# H-bro_gear.net
KiCad netlist of a schematic drawn in EAGLE
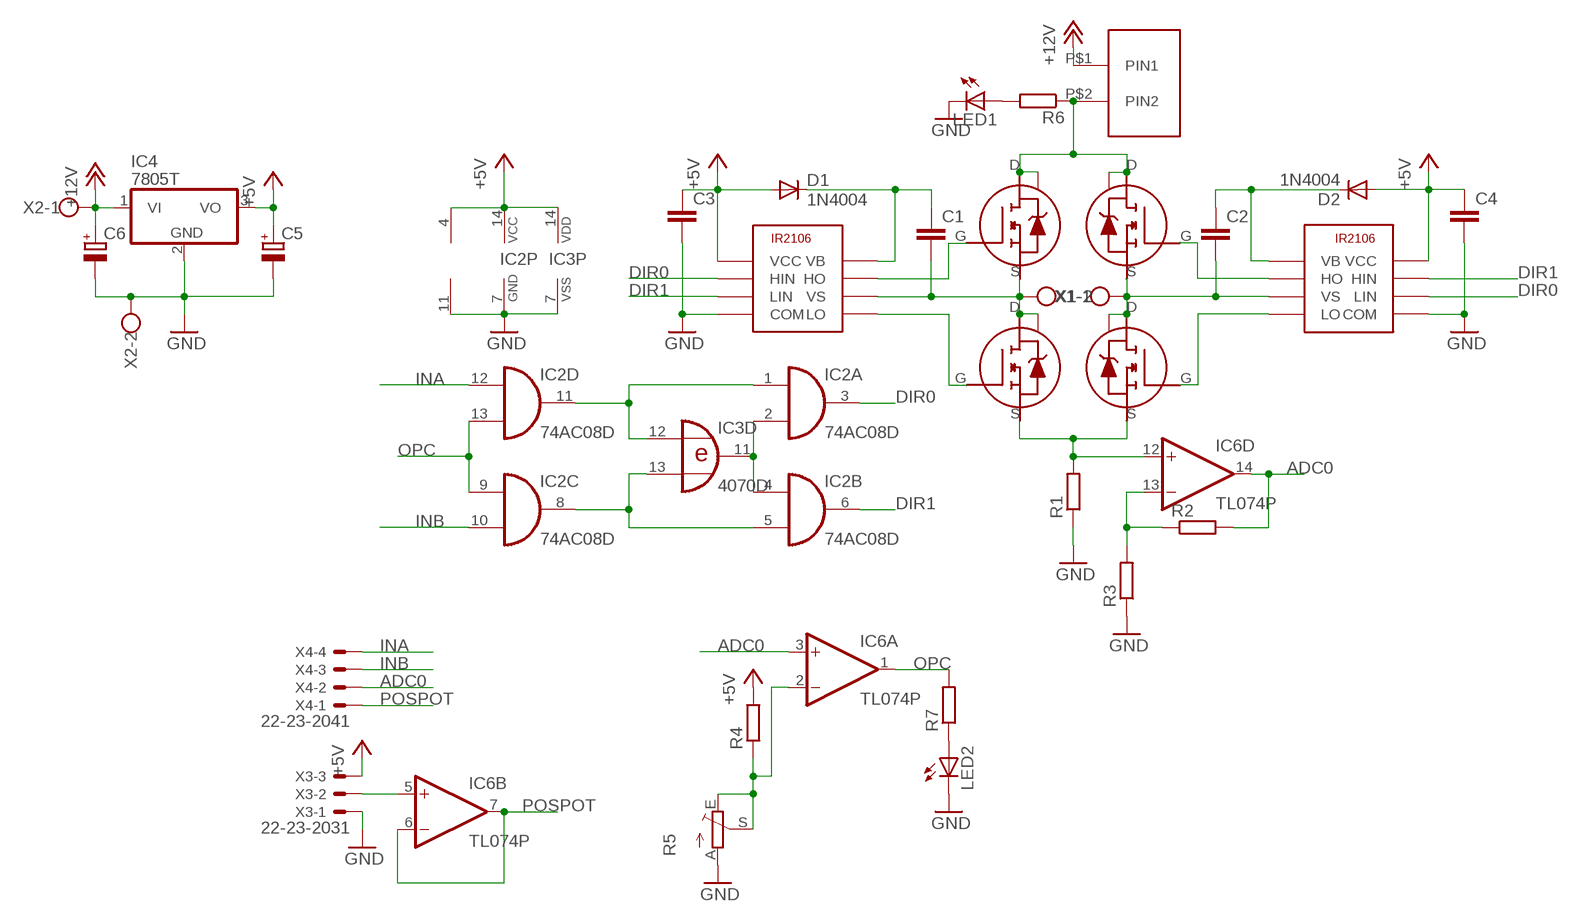
[diagram p0: schematic, sheet 1]

(export (version "E")
  (design (tool "Eeschema 10.0.6"))
  (components
    (comp (ref "C1")
      (value "C-EU050-025X075")
      (footprint "eagle-import:C050-025X075")
      (libsource (lib "eagle-import") (part "C-EU050-025X075"))
    )
    (comp (ref "C2")
      (value "C-EU050-025X075")
      (footprint "eagle-import:C050-025X075")
      (libsource (lib "eagle-import") (part "C-EU050-025X075"))
    )
    (comp (ref "C3")
      (value "C-EU050-025X075")
      (footprint "eagle-import:C050-025X075")
      (libsource (lib "eagle-import") (part "C-EU050-025X075"))
    )
    (comp (ref "C4")
      (value "C-EU050-025X075")
      (footprint "eagle-import:C050-025X075")
      (libsource (lib "eagle-import") (part "C-EU050-025X075"))
    )
    (comp (ref "C5")
      (value "CPOL-EUE15-5AXIAL")
      (footprint "eagle-import:E15-5")
      (libsource (lib "eagle-import") (part "CPOL-EUE15-5AXIAL"))
    )
    (comp (ref "C6")
      (value "CPOL-EUE15-5AXIAL")
      (footprint "eagle-import:E15-5")
      (libsource (lib "eagle-import") (part "CPOL-EUE15-5AXIAL"))
    )
    (comp (ref "D1")
      (value "1N4004")
      (footprint "eagle-import:DO41-10")
      (libsource (lib "eagle-import") (part "1N4004"))
    )
    (comp (ref "D2")
      (value "1N4004")
      (footprint "eagle-import:DO41-10")
      (libsource (lib "eagle-import") (part "1N4004"))
    )
    (comp (ref "IC2")
      (value "74AC08D")
      (footprint "eagle-import:SO14")
      (libsource (lib "eagle-import") (part "7408DAC"))
    )
    (comp (ref "IC3")
      (value "4070D")
      (footprint "eagle-import:SO14")
      (libsource (lib "eagle-import") (part "4070D"))
    )
    (comp (ref "IC4")
      (value "7805T")
      (footprint "eagle-import:TO220H")
      (libsource (lib "eagle-import") (part "78T05"))
    )
    (comp (ref "IC6")
      (value "TL074P")
      (footprint "eagle-import:DIL14")
      (libsource (lib "eagle-import") (part "TL074P"))
    )
    (comp (ref "LED1")
      (value "LED5MM")
      (footprint "eagle-import:LED5MM")
      (libsource (lib "eagle-import") (part "LED5MM"))
    )
    (comp (ref "LED2")
      (value "LED5MM")
      (footprint "eagle-import:LED5MM")
      (libsource (lib "eagle-import") (part "LED5MM"))
    )
    (comp (ref "R1")
      (value "R-EU_0309/12")
      (footprint "eagle-import:0309_12")
      (libsource (lib "eagle-import") (part "resistor_R-EU_0309/12"))
    )
    (comp (ref "R2")
      (value "R-EU_0204/7")
      (footprint "eagle-import:0204_7")
      (libsource (lib "eagle-import") (part "R-EU_0204/7"))
    )
    (comp (ref "R3")
      (value "R-EU_0204/7")
      (footprint "eagle-import:0204_7")
      (libsource (lib "eagle-import") (part "R-EU_0204/7"))
    )
    (comp (ref "R4")
      (value "R-EU_0204/7")
      (footprint "eagle-import:0204_7")
      (libsource (lib "eagle-import") (part "R-EU_0204/7"))
    )
    (comp (ref "R5")
      (value "TRIM_EU-RJ9W")
      (footprint "eagle-import:RJ9W")
      (libsource (lib "eagle-import") (part "TRIM_EU-RJ9W"))
    )
    (comp (ref "R6")
      (value "R-EU_0204/7")
      (footprint "eagle-import:0204_7")
      (libsource (lib "eagle-import") (part "R-EU_0204/7"))
    )
    (comp (ref "R7")
      (value "R-EU_0204/7")
      (footprint "eagle-import:0204_7")
      (libsource (lib "eagle-import") (part "R-EU_0204/7"))
    )
    (comp (ref "U$1")
      (value "IR2106")
      (footprint "eagle-import:IR2106")
      (libsource (lib "eagle-import") (part "IR2106"))
    )
    (comp (ref "U$2")
      (value "IR2106")
      (footprint "eagle-import:IR2106")
      (libsource (lib "eagle-import") (part "IR2106"))
    )
    (comp (ref "U$3")
      (value "STU95N5")
      (footprint "eagle-import:STU95N5")
      (libsource (lib "eagle-import") (part "STU95N5"))
    )
    (comp (ref "U$4")
      (value "STU95N5")
      (footprint "eagle-import:STU95N5")
      (libsource (lib "eagle-import") (part "STU95N5"))
    )
    (comp (ref "U$5")
      (value "STU95N5")
      (footprint "eagle-import:STU95N5")
      (libsource (lib "eagle-import") (part "STU95N5"))
    )
    (comp (ref "U$6")
      (value "STU95N5")
      (footprint "eagle-import:STU95N5")
      (libsource (lib "eagle-import") (part "STU95N5"))
    )
    (comp (ref "U$7")
      (value "LITTE_FUSE")
      (footprint "eagle-import:LITTE_FUSE_PAC")
      (libsource (lib "eagle-import") (part "LITTE_FUSE"))
    )
    (comp (ref "X1")
      (value "W237-102")
      (footprint "eagle-import:W237-102")
      (fields (field (name "MPN") "237-102"))
      (libsource (lib "eagle-import") (part "W237-102"))
    )
    (comp (ref "X2")
      (value "W237-102")
      (footprint "eagle-import:W237-102")
      (fields (field (name "MPN") "237-102"))
      (libsource (lib "eagle-import") (part "W237-102"))
    )
    (comp (ref "X3")
      (value "22-23-2031")
      (footprint "eagle-import:22-23-2031")
      (fields (field (name "MF") "MOLEX"))
      (libsource (lib "eagle-import") (part "22-23-2031"))
    )
    (comp (ref "X4")
      (value "22-23-2041")
      (footprint "eagle-import:22-23-2041")
      (fields (field (name "MF") "MOLEX"))
      (libsource (lib "eagle-import") (part "22-23-2041"))
    )
  )
  (nets
    (net (code "1") (name "+5V") (class "Default")
      (node (ref "C3") (pin "1") (pinfunction "1_1") (pintype "passive"))
      (node (ref "C4") (pin "1") (pinfunction "1_1") (pintype "passive"))
      (node (ref "C5") (pin "+") (pinfunction "+_+") (pintype "passive"))
      (node (ref "D1") (pin "A") (pinfunction "A_A") (pintype "passive"))
      (node (ref "D2") (pin "A") (pinfunction "A_A") (pintype "passive"))
      (node (ref "IC2") (pin "14") (pinfunction "VCC_14") (pintype "power_in"))
      (node (ref "IC3") (pin "14") (pinfunction "VDD_14") (pintype "power_in"))
      (node (ref "IC4") (pin "3") (pinfunction "VO_3") (pintype "passive"))
      (node (ref "IC6") (pin "4") (pinfunction "V+_4") (pintype "power_in"))
      (node (ref "R4") (pin "2") (pinfunction "2_2") (pintype "passive"))
      (node (ref "U$1") (pin "VCC") (pinfunction "VCC_VCC") (pintype "bidirectional"))
      (node (ref "U$2") (pin "VCC") (pinfunction "VCC_VCC") (pintype "bidirectional"))
      (node (ref "X3") (pin "3") (pinfunction "S_3") (pintype "passive"))
    )
    (net (code "2") (name "+12V") (class "Default")
      (node (ref "C6") (pin "+") (pinfunction "+_+") (pintype "passive"))
      (node (ref "IC4") (pin "1") (pinfunction "VI_1") (pintype "input"))
      (node (ref "U$7") (pin "P$1") (pinfunction "PIN1_P$1") (pintype "bidirectional"))
      (node (ref "X2") (pin "1") (pinfunction "KL_1") (pintype "passive"))
    )
    (net (code "3") (name "/ADC0") (class "Default")
      (node (ref "IC6") (pin "14") (pinfunction "OUT_14") (pintype "output"))
      (node (ref "IC6") (pin "3") (pinfunction "+IN_3") (pintype "input"))
      (node (ref "R2") (pin "2") (pinfunction "2_2") (pintype "passive"))
      (node (ref "X4") (pin "2") (pinfunction "S_2") (pintype "passive"))
    )
    (net (code "4") (name "/DIR0") (class "Default")
      (node (ref "IC2") (pin "3") (pinfunction "O_3") (pintype "output"))
      (node (ref "U$1") (pin "HIN") (pinfunction "HIN_HIN") (pintype "bidirectional"))
      (node (ref "U$2") (pin "LIN") (pinfunction "LIN_LIN") (pintype "bidirectional"))
    )
    (net (code "5") (name "/DIR1") (class "Default")
      (node (ref "IC2") (pin "6") (pinfunction "O_6") (pintype "output"))
      (node (ref "U$1") (pin "LIN") (pinfunction "LIN_LIN") (pintype "bidirectional"))
      (node (ref "U$2") (pin "HIN") (pinfunction "HIN_HIN") (pintype "bidirectional"))
    )
    (net (code "6") (name "/INA") (class "Default")
      (node (ref "IC2") (pin "12") (pinfunction "I0_12") (pintype "input"))
      (node (ref "X4") (pin "4") (pinfunction "S_4") (pintype "passive"))
    )
    (net (code "7") (name "/INB") (class "Default")
      (node (ref "IC2") (pin "10") (pinfunction "I1_10") (pintype "input"))
      (node (ref "X4") (pin "3") (pinfunction "S_3") (pintype "passive"))
    )
    (net (code "8") (name "/OPC") (class "Default")
      (node (ref "IC2") (pin "13") (pinfunction "I1_13") (pintype "input"))
      (node (ref "IC2") (pin "9") (pinfunction "I0_9") (pintype "input"))
      (node (ref "IC6") (pin "1") (pinfunction "OUT_1") (pintype "output"))
      (node (ref "R7") (pin "2") (pinfunction "2_2") (pintype "passive"))
    )
    (net (code "9") (name "/POSPOT") (class "Default")
      (node (ref "IC6") (pin "6") (pinfunction "-IN_6") (pintype "input"))
      (node (ref "IC6") (pin "7") (pinfunction "OUT_7") (pintype "output"))
      (node (ref "X4") (pin "1") (pinfunction "S_1") (pintype "passive"))
    )
    (net (code "10") (name "GND") (class "Default")
      (node (ref "C3") (pin "2") (pinfunction "2_2") (pintype "passive"))
      (node (ref "C4") (pin "2") (pinfunction "2_2") (pintype "passive"))
      (node (ref "C5") (pin "-") (pinfunction "-_-") (pintype "passive"))
      (node (ref "C6") (pin "-") (pinfunction "-_-") (pintype "passive"))
      (node (ref "IC2") (pin "7") (pinfunction "GND_7") (pintype "power_in"))
      (node (ref "IC3") (pin "7") (pinfunction "VSS_7") (pintype "power_in"))
      (node (ref "IC4") (pin "2") (pinfunction "GND_2") (pintype "passive"))
      (node (ref "IC6") (pin "11") (pinfunction "V-_11") (pintype "power_in"))
      (node (ref "LED1") (pin "K") (pinfunction "C_K") (pintype "passive"))
      (node (ref "LED2") (pin "K") (pinfunction "C_K") (pintype "passive"))
      (node (ref "R1") (pin "1") (pinfunction "1_1") (pintype "passive"))
      (node (ref "R3") (pin "1") (pinfunction "1_1") (pintype "passive"))
      (node (ref "R5") (pin "A") (pinfunction "A_A") (pintype "passive"))
      (node (ref "U$1") (pin "COM") (pinfunction "COM_COM") (pintype "bidirectional"))
      (node (ref "U$2") (pin "COM") (pinfunction "COM_COM") (pintype "bidirectional"))
      (node (ref "X2") (pin "2") (pinfunction "KL_2") (pintype "passive"))
      (node (ref "X3") (pin "1") (pinfunction "S_1") (pintype "passive"))
    )
    (net (code "11") (name "Net-(C1-Pad1)") (class "Default")
      (node (ref "C1") (pin "1") (pinfunction "1_1") (pintype "passive"))
      (node (ref "D1") (pin "C") (pinfunction "C_C") (pintype "passive"))
      (node (ref "U$1") (pin "VB") (pinfunction "VB_VB") (pintype "bidirectional"))
    )
    (net (code "12") (name "Net-(C2-Pad1)") (class "Default")
      (node (ref "C2") (pin "1") (pinfunction "1_1") (pintype "passive"))
      (node (ref "D2") (pin "C") (pinfunction "C_C") (pintype "passive"))
      (node (ref "U$2") (pin "VB") (pinfunction "VB_VB") (pintype "bidirectional"))
    )
    (net (code "13") (name "Net-(IC2A-I0)") (class "Default")
      (node (ref "IC2") (pin "1") (pinfunction "I0_1") (pintype "input"))
      (node (ref "IC2") (pin "11") (pinfunction "O_11") (pintype "output"))
      (node (ref "IC3") (pin "12") (pinfunction "I0_12") (pintype "input"))
    )
    (net (code "14") (name "Net-(IC2A-I1)") (class "Default")
      (node (ref "IC2") (pin "2") (pinfunction "I1_2") (pintype "input"))
      (node (ref "IC2") (pin "4") (pinfunction "I0_4") (pintype "input"))
      (node (ref "IC3") (pin "11") (pinfunction "O_11") (pintype "output"))
    )
    (net (code "15") (name "Net-(IC2B-I1)") (class "Default")
      (node (ref "IC2") (pin "5") (pinfunction "I1_5") (pintype "input"))
      (node (ref "IC2") (pin "8") (pinfunction "O_8") (pintype "output"))
      (node (ref "IC3") (pin "13") (pinfunction "I1_13") (pintype "input"))
    )
    (net (code "16") (name "Net-(IC6A--IN)") (class "Default")
      (node (ref "IC6") (pin "2") (pinfunction "-IN_2") (pintype "input"))
      (node (ref "R4") (pin "1") (pinfunction "1_1") (pintype "passive"))
      (node (ref "R5") (pin "E") (pinfunction "E_E") (pintype "passive"))
      (node (ref "R5") (pin "S") (pinfunction "S_S") (pintype "passive"))
    )
    (net (code "17") (name "Net-(IC6B-+IN)") (class "Default")
      (node (ref "IC6") (pin "5") (pinfunction "+IN_5") (pintype "input"))
      (node (ref "X3") (pin "2") (pinfunction "S_2") (pintype "passive"))
    )
    (net (code "18") (name "Net-(IC6D-+IN)") (class "Default")
      (node (ref "IC6") (pin "12") (pinfunction "+IN_12") (pintype "input"))
      (node (ref "R1") (pin "2") (pinfunction "2_2") (pintype "passive"))
      (node (ref "U$4") (pin "S") (pinfunction "S_S") (pintype "bidirectional"))
      (node (ref "U$5") (pin "S") (pinfunction "S_S") (pintype "bidirectional"))
    )
    (net (code "19") (name "Net-(IC6D--IN)") (class "Default")
      (node (ref "IC6") (pin "13") (pinfunction "-IN_13") (pintype "input"))
      (node (ref "R2") (pin "1") (pinfunction "1_1") (pintype "passive"))
      (node (ref "R3") (pin "2") (pinfunction "2_2") (pintype "passive"))
    )
    (net (code "20") (name "Net-(LED1-PadA)") (class "Default")
      (node (ref "LED1") (pin "A") (pinfunction "A_A") (pintype "passive"))
      (node (ref "R6") (pin "2") (pinfunction "2_2") (pintype "passive"))
    )
    (net (code "21") (name "Net-(LED2-PadA)") (class "Default")
      (node (ref "LED2") (pin "A") (pinfunction "A_A") (pintype "passive"))
      (node (ref "R7") (pin "1") (pinfunction "1_1") (pintype "passive"))
    )
    (net (code "22") (name "Net-(U$1-PadHO)") (class "Default")
      (node (ref "U$1") (pin "HO") (pinfunction "HO_HO") (pintype "bidirectional"))
      (node (ref "U$3") (pin "G") (pinfunction "G_G") (pintype "bidirectional"))
    )
    (net (code "23") (name "Net-(U$1-PadLO)") (class "Default")
      (node (ref "U$1") (pin "LO") (pinfunction "LO_LO") (pintype "bidirectional"))
      (node (ref "U$4") (pin "G") (pinfunction "G_G") (pintype "bidirectional"))
    )
    (net (code "24") (name "Net-(U$2-PadHO)") (class "Default")
      (node (ref "U$2") (pin "HO") (pinfunction "HO_HO") (pintype "bidirectional"))
      (node (ref "U$6") (pin "G") (pinfunction "G_G") (pintype "bidirectional"))
    )
    (net (code "25") (name "Net-(U$2-PadLO)") (class "Default")
      (node (ref "U$2") (pin "LO") (pinfunction "LO_LO") (pintype "bidirectional"))
      (node (ref "U$5") (pin "G") (pinfunction "G_G") (pintype "bidirectional"))
    )
    (net (code "26") (name "Net-(U$7-PIN2)") (class "Default")
      (node (ref "R6") (pin "1") (pinfunction "1_1") (pintype "passive"))
      (node (ref "U$3") (pin "D") (pinfunction "D_D") (pintype "bidirectional"))
      (node (ref "U$3") (pin "TAB") (pinfunction "TAB_TAB") (pintype "bidirectional"))
      (node (ref "U$6") (pin "D") (pinfunction "D_D") (pintype "bidirectional"))
      (node (ref "U$6") (pin "TAB") (pinfunction "TAB_TAB") (pintype "bidirectional"))
      (node (ref "U$7") (pin "P$2") (pinfunction "PIN2_P$2") (pintype "bidirectional"))
    )
    (net (code "27") (name "Net-(X1A-KL)") (class "Default")
      (node (ref "C2") (pin "2") (pinfunction "2_2") (pintype "passive"))
      (node (ref "U$2") (pin "VS") (pinfunction "VS_VS") (pintype "bidirectional"))
      (node (ref "U$5") (pin "D") (pinfunction "D_D") (pintype "bidirectional"))
      (node (ref "U$5") (pin "TAB") (pinfunction "TAB_TAB") (pintype "bidirectional"))
      (node (ref "U$6") (pin "S") (pinfunction "S_S") (pintype "bidirectional"))
      (node (ref "X1") (pin "1") (pinfunction "KL_1") (pintype "passive"))
    )
    (net (code "28") (name "Net-(X1B-KL)") (class "Default")
      (node (ref "C1") (pin "2") (pinfunction "2_2") (pintype "passive"))
      (node (ref "U$1") (pin "VS") (pinfunction "VS_VS") (pintype "bidirectional"))
      (node (ref "U$3") (pin "S") (pinfunction "S_S") (pintype "bidirectional"))
      (node (ref "U$4") (pin "D") (pinfunction "D_D") (pintype "bidirectional"))
      (node (ref "U$4") (pin "TAB") (pinfunction "TAB_TAB") (pintype "bidirectional"))
      (node (ref "X1") (pin "2") (pinfunction "KL_2") (pintype "passive"))
    )
  )
)
